# KeyboardSidepanel.net
KiCad netlist of a schematic drawn in EAGLE
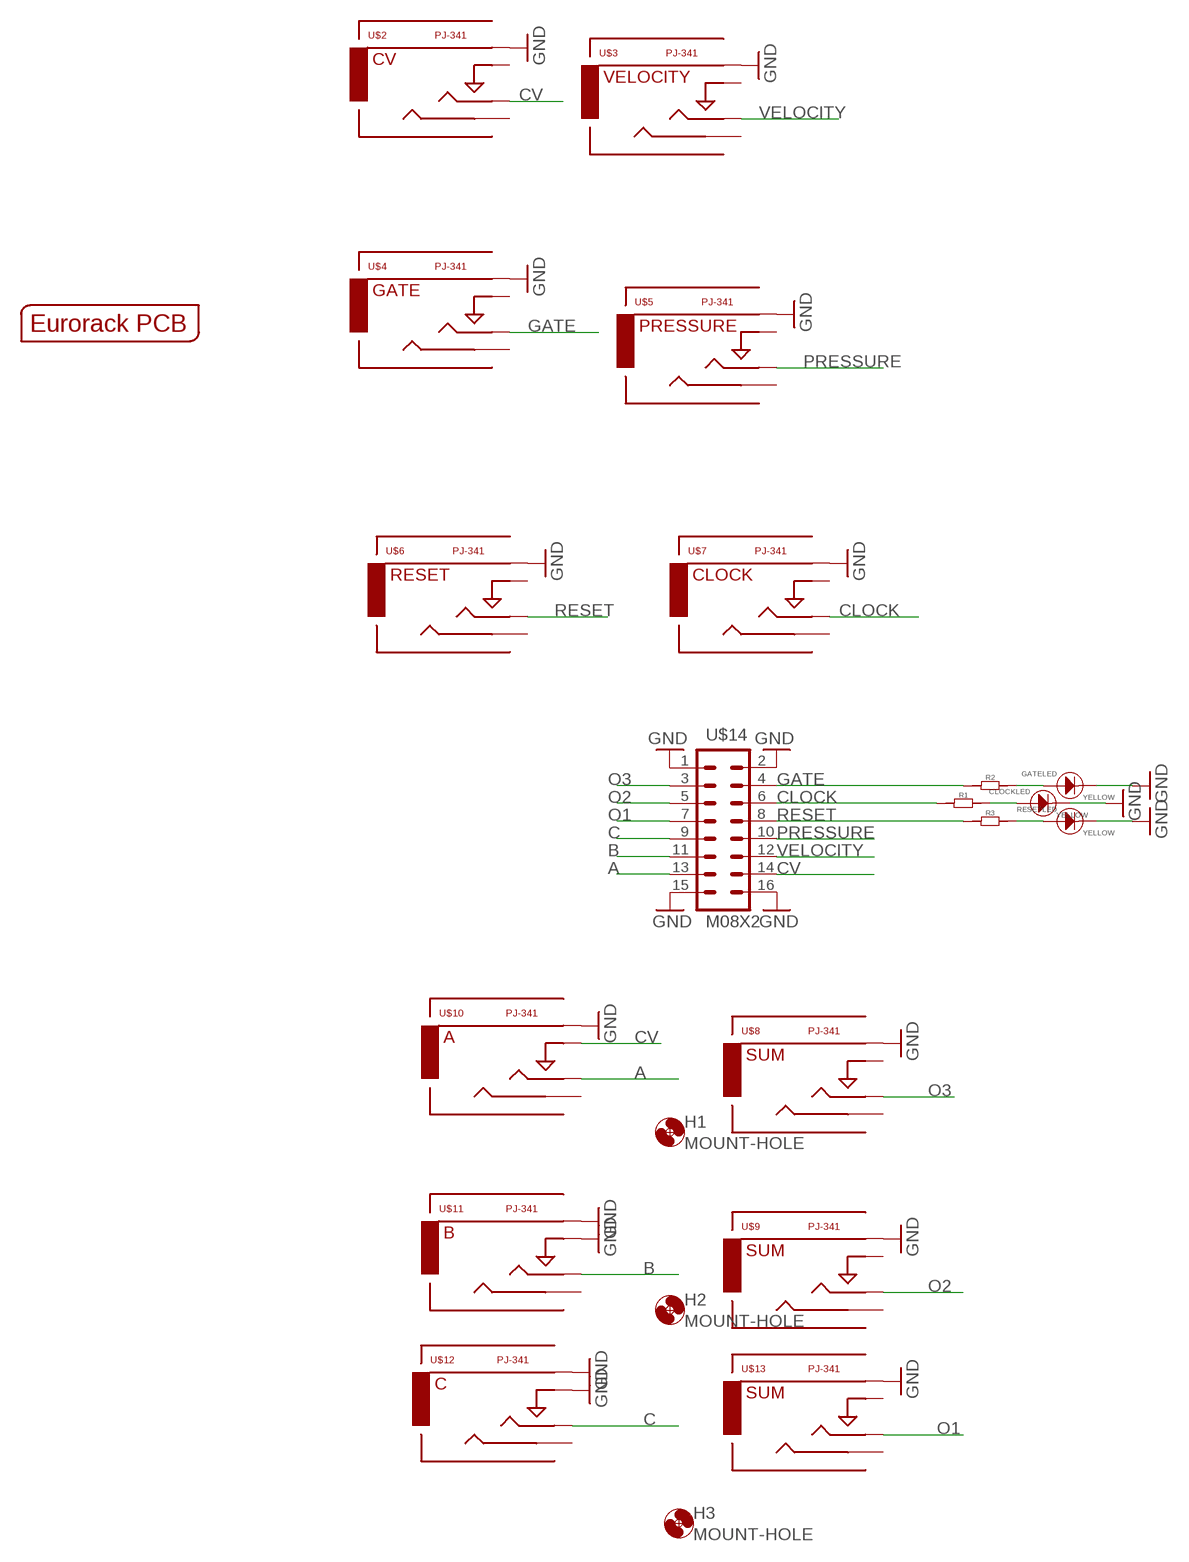
[diagram p0: schematic, sheet 1]

(export (version "E")
  (design (tool "Eeschema 10.0.6"))
  (components
    (comp (ref "CLOCKLED")
      (value "YELLOW")
      (footprint "eagle-import:3MMLED")
      (libsource (lib "eagle-import") (part "LED3MM"))
    )
    (comp (ref "GATELED")
      (value "YELLOW")
      (footprint "eagle-import:3MMLED")
      (libsource (lib "eagle-import") (part "LED3MM"))
    )
    (comp (ref "H1")
      (value "MOUNT-HOLE")
      (footprint "eagle-import:3.2-NOMARKINGS-SMALLSAFEZONE")
      (libsource (lib "eagle-import") (part "MOUNT-HOLE"))
    )
    (comp (ref "H2")
      (value "MOUNT-HOLE")
      (footprint "eagle-import:3.2-NOMARKINGS-SMALLSAFEZONE")
      (libsource (lib "eagle-import") (part "MOUNT-HOLE"))
    )
    (comp (ref "H3")
      (value "MOUNT-HOLE")
      (footprint "eagle-import:3.2-NOMARKINGS-SMALLSAFEZONE")
      (libsource (lib "eagle-import") (part "MOUNT-HOLE"))
    )
    (comp (ref "R1")
      (value "R-0603")
      (footprint "eagle-import:R0603")
      (libsource (lib "eagle-import") (part "R-0603"))
    )
    (comp (ref "R2")
      (value "R-0603")
      (footprint "eagle-import:R0603")
      (libsource (lib "eagle-import") (part "R-0603"))
    )
    (comp (ref "R3")
      (value "R-0603")
      (footprint "eagle-import:R0603")
      (libsource (lib "eagle-import") (part "R-0603"))
    )
    (comp (ref "RESETLED")
      (value "YELLOW")
      (footprint "eagle-import:3MMLED")
      (libsource (lib "eagle-import") (part "LED3MM"))
    )
    (comp (ref "U$1")
      (value "EURORACK_PCB6HP_10CM")
      (footprint "eagle-import:EURORACK6HPPCB_10CMTALL")
      (libsource (lib "eagle-import") (part "EURORACK_PCB6HP_10CM"))
    )
    (comp (ref "U$2")
      (value "PJ-341")
      (footprint "eagle-import:3.5MM-JACK-SWITCH-13MM-OUTPUT")
      (fields (field (name "DESC") "CV"))
      (libsource (lib "eagle-import") (part "AUDIO-JACKOUTPUT"))
    )
    (comp (ref "U$3")
      (value "PJ-341")
      (footprint "eagle-import:3.5MM-JACK-SWITCH-13MM-OUTPUT")
      (fields (field (name "DESC") "VELOCITY"))
      (libsource (lib "eagle-import") (part "AUDIO-JACKOUTPUT"))
    )
    (comp (ref "U$4")
      (value "PJ-341")
      (footprint "eagle-import:3.5MM-JACK-SWITCH-13MM-OUTPUT")
      (fields (field (name "DESC") "GATE"))
      (libsource (lib "eagle-import") (part "AUDIO-JACKOUTPUT"))
    )
    (comp (ref "U$5")
      (value "PJ-341")
      (footprint "eagle-import:3.5MM-JACK-SWITCH-13MM-OUTPUT")
      (fields (field (name "DESC") "PRESSURE"))
      (libsource (lib "eagle-import") (part "AUDIO-JACKOUTPUT"))
    )
    (comp (ref "U$6")
      (value "PJ-341")
      (footprint "eagle-import:3.5MM-JACK-SWITCH-13MM-OUTPUT")
      (fields (field (name "DESC") "RESET"))
      (libsource (lib "eagle-import") (part "AUDIO-JACKOUTPUT"))
    )
    (comp (ref "U$7")
      (value "PJ-341")
      (footprint "eagle-import:3.5MM-JACK-SWITCH-13MM-OUTPUT")
      (fields (field (name "DESC") "CLOCK"))
      (libsource (lib "eagle-import") (part "AUDIO-JACKOUTPUT"))
    )
    (comp (ref "U$8")
      (value "PJ-341")
      (footprint "eagle-import:3.5MM-JACK-SWITCH-13MM-OUTPUT")
      (fields (field (name "DESC") "SUM"))
      (libsource (lib "eagle-import") (part "AUDIO-JACKOUTPUT"))
    )
    (comp (ref "U$9")
      (value "PJ-341")
      (footprint "eagle-import:3.5MM-JACK-SWITCH-13MM-OUTPUT")
      (fields (field (name "DESC") "SUM"))
      (libsource (lib "eagle-import") (part "AUDIO-JACKOUTPUT"))
    )
    (comp (ref "U$10")
      (value "PJ-341")
      (footprint "eagle-import:3.5MM-JACK-SWITCH-13MM-INPUT")
      (fields (field (name "DESC") "A"))
      (libsource (lib "eagle-import") (part "AUDIO-JACKINPUT"))
    )
    (comp (ref "U$11")
      (value "PJ-341")
      (footprint "eagle-import:3.5MM-JACK-SWITCH-13MM-INPUT")
      (fields (field (name "DESC") "B"))
      (libsource (lib "eagle-import") (part "AUDIO-JACKINPUT"))
    )
    (comp (ref "U$12")
      (value "PJ-341")
      (footprint "eagle-import:3.5MM-JACK-SWITCH-13MM-INPUT")
      (fields (field (name "DESC") "C"))
      (libsource (lib "eagle-import") (part "AUDIO-JACKINPUT"))
    )
    (comp (ref "U$13")
      (value "PJ-341")
      (footprint "eagle-import:3.5MM-JACK-SWITCH-13MM-OUTPUT")
      (fields (field (name "DESC") "SUM"))
      (libsource (lib "eagle-import") (part "AUDIO-JACKOUTPUT"))
    )
    (comp (ref "U$14")
      (value "M08X2")
      (footprint "eagle-import:2X8")
      (libsource (lib "eagle-import") (part "M08X2"))
    )
  )
  (nets
    (net (code "1") (name "/A") (class "Default")
      (node (ref "U$10") (pin "TIP@3") (pinfunction "TIP_TIP@3") (pintype "bidirectional"))
      (node (ref "U$14") (pin "13") (pinfunction "13_13") (pintype "passive"))
    )
    (net (code "2") (name "/B") (class "Default")
      (node (ref "U$11") (pin "TIP@3") (pinfunction "TIP_TIP@3") (pintype "bidirectional"))
      (node (ref "U$14") (pin "11") (pinfunction "11_11") (pintype "passive"))
    )
    (net (code "3") (name "/C") (class "Default")
      (node (ref "U$12") (pin "TIP@3") (pinfunction "TIP_TIP@3") (pintype "bidirectional"))
      (node (ref "U$14") (pin "9") (pinfunction "9_9") (pintype "passive"))
    )
    (net (code "4") (name "/CLOCK") (class "Default")
      (node (ref "R1") (pin "1") (pinfunction "1_1") (pintype "bidirectional"))
      (node (ref "U$14") (pin "6") (pinfunction "6_6") (pintype "passive"))
      (node (ref "U$7") (pin "TIP@3") (pinfunction "TIP_TIP@3") (pintype "bidirectional"))
    )
    (net (code "5") (name "/CV") (class "Default")
      (node (ref "U$10") (pin "SWITCH@3") (pinfunction "SWITCH_SWITCH@3") (pintype "bidirectional"))
      (node (ref "U$14") (pin "14") (pinfunction "14_14") (pintype "passive"))
      (node (ref "U$2") (pin "TIP@3") (pinfunction "TIP_TIP@3") (pintype "bidirectional"))
    )
    (net (code "6") (name "/GATE") (class "Default")
      (node (ref "R2") (pin "1") (pinfunction "1_1") (pintype "bidirectional"))
      (node (ref "U$14") (pin "4") (pinfunction "4_4") (pintype "passive"))
      (node (ref "U$4") (pin "TIP@3") (pinfunction "TIP_TIP@3") (pintype "bidirectional"))
    )
    (net (code "7") (name "/O1") (class "Default")
      (node (ref "U$13") (pin "TIP@3") (pinfunction "TIP_TIP@3") (pintype "bidirectional"))
      (node (ref "U$14") (pin "7") (pinfunction "7_7") (pintype "passive"))
    )
    (net (code "8") (name "/O2") (class "Default")
      (node (ref "U$14") (pin "5") (pinfunction "5_5") (pintype "passive"))
      (node (ref "U$9") (pin "TIP@3") (pinfunction "TIP_TIP@3") (pintype "bidirectional"))
    )
    (net (code "9") (name "/O3") (class "Default")
      (node (ref "U$14") (pin "3") (pinfunction "3_3") (pintype "passive"))
      (node (ref "U$8") (pin "TIP@3") (pinfunction "TIP_TIP@3") (pintype "bidirectional"))
    )
    (net (code "10") (name "/PRESSURE") (class "Default")
      (node (ref "U$14") (pin "10") (pinfunction "10_10") (pintype "passive"))
      (node (ref "U$5") (pin "TIP@3") (pinfunction "TIP_TIP@3") (pintype "bidirectional"))
    )
    (net (code "11") (name "/RESET") (class "Default")
      (node (ref "R3") (pin "1") (pinfunction "1_1") (pintype "bidirectional"))
      (node (ref "U$14") (pin "8") (pinfunction "8_8") (pintype "passive"))
      (node (ref "U$6") (pin "TIP@3") (pinfunction "TIP_TIP@3") (pintype "bidirectional"))
    )
    (net (code "12") (name "/VELOCITY") (class "Default")
      (node (ref "U$14") (pin "12") (pinfunction "12_12") (pintype "passive"))
      (node (ref "U$3") (pin "TIP@3") (pinfunction "TIP_TIP@3") (pintype "bidirectional"))
    )
    (net (code "13") (name "GND") (class "Default")
      (node (ref "CLOCKLED") (pin "-") (pinfunction "-_-") (pintype "passive"))
      (node (ref "GATELED") (pin "-") (pinfunction "-_-") (pintype "passive"))
      (node (ref "RESETLED") (pin "-") (pinfunction "-_-") (pintype "passive"))
      (node (ref "U$10") (pin "RING@3") (pinfunction "RING_RING@3") (pintype "bidirectional"))
      (node (ref "U$11") (pin "RING@3") (pinfunction "RING_RING@3") (pintype "bidirectional"))
      (node (ref "U$11") (pin "SWITCH@3") (pinfunction "SWITCH_SWITCH@3") (pintype "bidirectional"))
      (node (ref "U$12") (pin "RING@3") (pinfunction "RING_RING@3") (pintype "bidirectional"))
      (node (ref "U$12") (pin "SWITCH@3") (pinfunction "SWITCH_SWITCH@3") (pintype "bidirectional"))
      (node (ref "U$13") (pin "RING@3") (pinfunction "RING_RING@3") (pintype "bidirectional"))
      (node (ref "U$14") (pin "1") (pinfunction "1_1") (pintype "passive"))
      (node (ref "U$14") (pin "15") (pinfunction "15_15") (pintype "passive"))
      (node (ref "U$14") (pin "16") (pinfunction "16_16") (pintype "passive"))
      (node (ref "U$14") (pin "2") (pinfunction "2_2") (pintype "passive"))
      (node (ref "U$2") (pin "RING@3") (pinfunction "RING_RING@3") (pintype "bidirectional"))
      (node (ref "U$3") (pin "RING@3") (pinfunction "RING_RING@3") (pintype "bidirectional"))
      (node (ref "U$4") (pin "RING@3") (pinfunction "RING_RING@3") (pintype "bidirectional"))
      (node (ref "U$5") (pin "RING@3") (pinfunction "RING_RING@3") (pintype "bidirectional"))
      (node (ref "U$6") (pin "RING@3") (pinfunction "RING_RING@3") (pintype "bidirectional"))
      (node (ref "U$7") (pin "RING@3") (pinfunction "RING_RING@3") (pintype "bidirectional"))
      (node (ref "U$8") (pin "RING@3") (pinfunction "RING_RING@3") (pintype "bidirectional"))
      (node (ref "U$9") (pin "RING@3") (pinfunction "RING_RING@3") (pintype "bidirectional"))
    )
    (net (code "14") (name "Net-(CLOCKLED-Pad+)") (class "Default")
      (node (ref "CLOCKLED") (pin "+") (pinfunction "+_+") (pintype "passive"))
      (node (ref "R1") (pin "2") (pinfunction "2_2") (pintype "bidirectional"))
    )
    (net (code "15") (name "Net-(GATELED-Pad+)") (class "Default")
      (node (ref "GATELED") (pin "+") (pinfunction "+_+") (pintype "passive"))
      (node (ref "R2") (pin "2") (pinfunction "2_2") (pintype "bidirectional"))
    )
    (net (code "16") (name "Net-(R3-Pad2)") (class "Default")
      (node (ref "R3") (pin "2") (pinfunction "2_2") (pintype "bidirectional"))
      (node (ref "RESETLED") (pin "+") (pinfunction "+_+") (pintype "passive"))
    )
    (net (code "17") (name "unconnected-(U$2-SECOND-PadSECOND@3)") (class "Default")
      (node (ref "U$2") (pin "SECOND@3") (pinfunction "SECOND_SECOND@3") (pintype "bidirectional"))
    )
    (net (code "18") (name "unconnected-(U$2-SWITCH-PadSWITCH@3)") (class "Default")
      (node (ref "U$2") (pin "SWITCH@3") (pinfunction "SWITCH_SWITCH@3") (pintype "bidirectional"))
    )
    (net (code "19") (name "unconnected-(U$3-SECOND-PadSECOND@3)") (class "Default")
      (node (ref "U$3") (pin "SECOND@3") (pinfunction "SECOND_SECOND@3") (pintype "bidirectional"))
    )
    (net (code "20") (name "unconnected-(U$3-SWITCH-PadSWITCH@3)") (class "Default")
      (node (ref "U$3") (pin "SWITCH@3") (pinfunction "SWITCH_SWITCH@3") (pintype "bidirectional"))
    )
    (net (code "21") (name "unconnected-(U$4-SECOND-PadSECOND@3)") (class "Default")
      (node (ref "U$4") (pin "SECOND@3") (pinfunction "SECOND_SECOND@3") (pintype "bidirectional"))
    )
    (net (code "22") (name "unconnected-(U$4-SWITCH-PadSWITCH@3)") (class "Default")
      (node (ref "U$4") (pin "SWITCH@3") (pinfunction "SWITCH_SWITCH@3") (pintype "bidirectional"))
    )
    (net (code "23") (name "unconnected-(U$5-SECOND-PadSECOND@3)") (class "Default")
      (node (ref "U$5") (pin "SECOND@3") (pinfunction "SECOND_SECOND@3") (pintype "bidirectional"))
    )
    (net (code "24") (name "unconnected-(U$5-SWITCH-PadSWITCH@3)") (class "Default")
      (node (ref "U$5") (pin "SWITCH@3") (pinfunction "SWITCH_SWITCH@3") (pintype "bidirectional"))
    )
    (net (code "25") (name "unconnected-(U$6-SECOND-PadSECOND@3)") (class "Default")
      (node (ref "U$6") (pin "SECOND@3") (pinfunction "SECOND_SECOND@3") (pintype "bidirectional"))
    )
    (net (code "26") (name "unconnected-(U$6-SWITCH-PadSWITCH@3)") (class "Default")
      (node (ref "U$6") (pin "SWITCH@3") (pinfunction "SWITCH_SWITCH@3") (pintype "bidirectional"))
    )
    (net (code "27") (name "unconnected-(U$7-SECOND-PadSECOND@3)") (class "Default")
      (node (ref "U$7") (pin "SECOND@3") (pinfunction "SECOND_SECOND@3") (pintype "bidirectional"))
    )
    (net (code "28") (name "unconnected-(U$7-SWITCH-PadSWITCH@3)") (class "Default")
      (node (ref "U$7") (pin "SWITCH@3") (pinfunction "SWITCH_SWITCH@3") (pintype "bidirectional"))
    )
    (net (code "29") (name "unconnected-(U$8-SECOND-PadSECOND@3)") (class "Default")
      (node (ref "U$8") (pin "SECOND@3") (pinfunction "SECOND_SECOND@3") (pintype "bidirectional"))
    )
    (net (code "30") (name "unconnected-(U$8-SWITCH-PadSWITCH@3)") (class "Default")
      (node (ref "U$8") (pin "SWITCH@3") (pinfunction "SWITCH_SWITCH@3") (pintype "bidirectional"))
    )
    (net (code "31") (name "unconnected-(U$9-SECOND-PadSECOND@3)") (class "Default")
      (node (ref "U$9") (pin "SECOND@3") (pinfunction "SECOND_SECOND@3") (pintype "bidirectional"))
    )
    (net (code "32") (name "unconnected-(U$9-SWITCH-PadSWITCH@3)") (class "Default")
      (node (ref "U$9") (pin "SWITCH@3") (pinfunction "SWITCH_SWITCH@3") (pintype "bidirectional"))
    )
    (net (code "33") (name "unconnected-(U$10-SECOND-PadSECOND@3)") (class "Default")
      (node (ref "U$10") (pin "SECOND@3") (pinfunction "SECOND_SECOND@3") (pintype "bidirectional"))
    )
    (net (code "34") (name "unconnected-(U$11-SECOND-PadSECOND@3)") (class "Default")
      (node (ref "U$11") (pin "SECOND@3") (pinfunction "SECOND_SECOND@3") (pintype "bidirectional"))
    )
    (net (code "35") (name "unconnected-(U$12-SECOND-PadSECOND@3)") (class "Default")
      (node (ref "U$12") (pin "SECOND@3") (pinfunction "SECOND_SECOND@3") (pintype "bidirectional"))
    )
    (net (code "36") (name "unconnected-(U$13-SECOND-PadSECOND@3)") (class "Default")
      (node (ref "U$13") (pin "SECOND@3") (pinfunction "SECOND_SECOND@3") (pintype "bidirectional"))
    )
    (net (code "37") (name "unconnected-(U$13-SWITCH-PadSWITCH@3)") (class "Default")
      (node (ref "U$13") (pin "SWITCH@3") (pinfunction "SWITCH_SWITCH@3") (pintype "bidirectional"))
    )
  )
)
